# SectionD_v1_0.net
KiCad netlist of a schematic drawn in Altium Designer
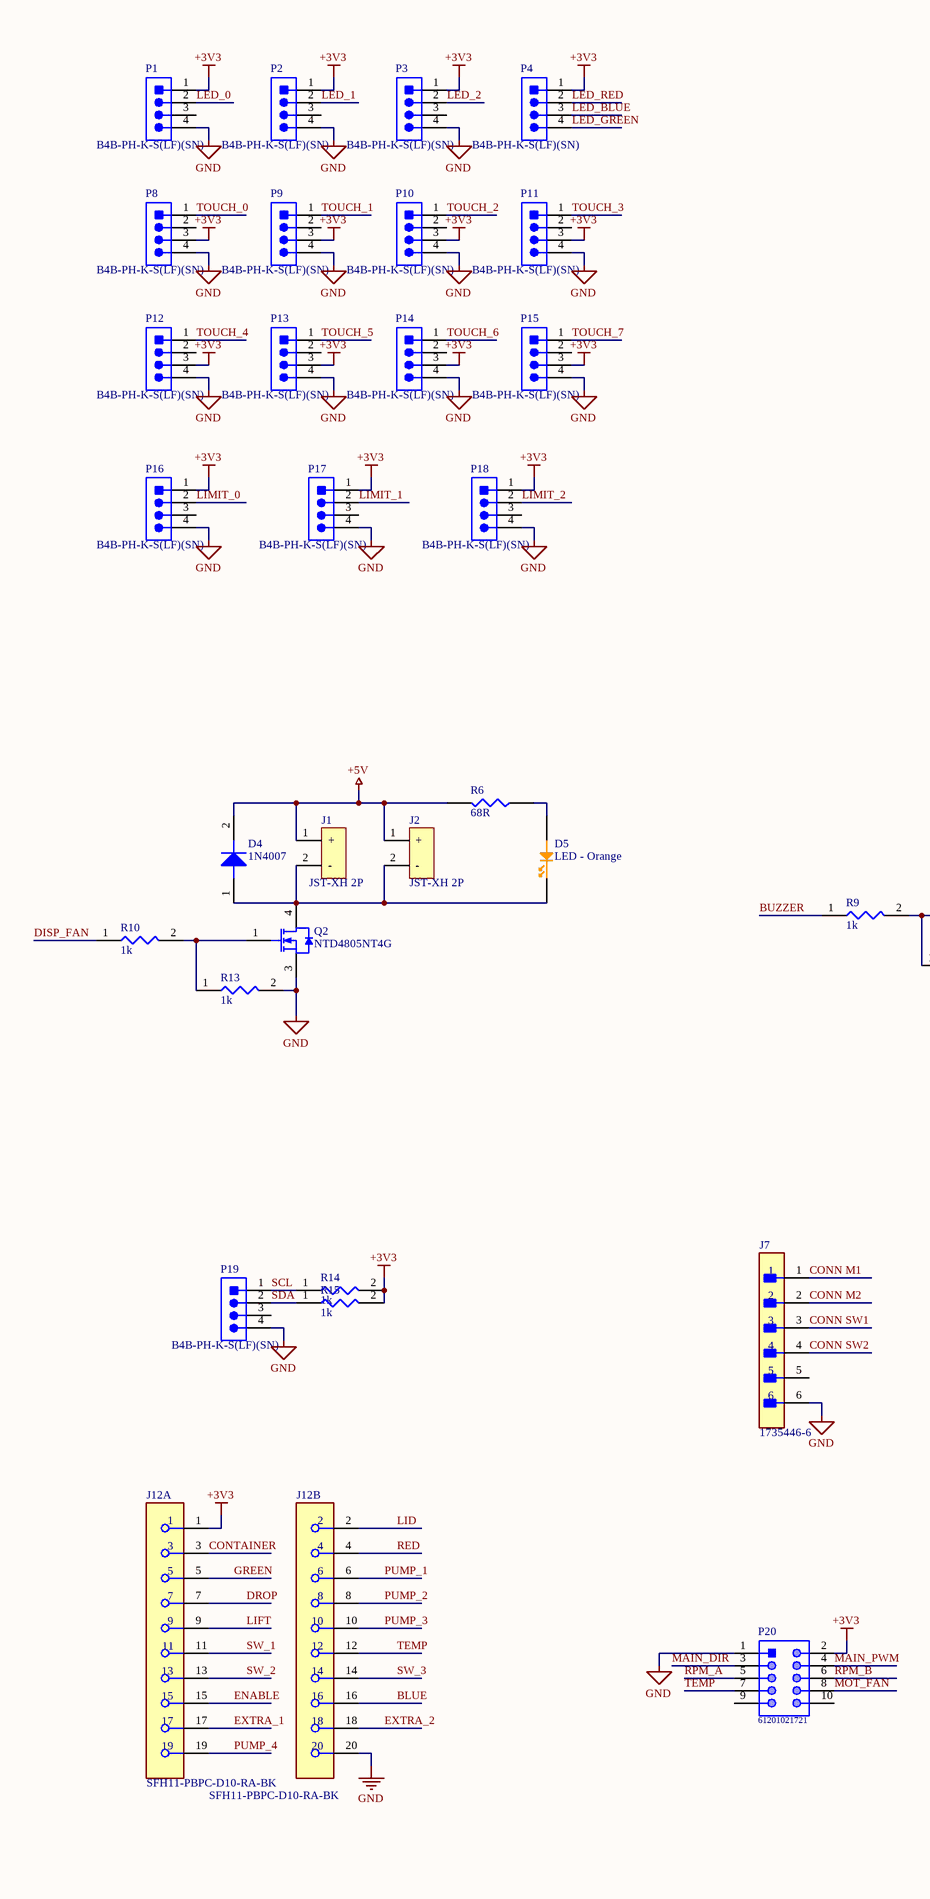
[diagram p0: SectionD_v1.0.SchDoc, left]
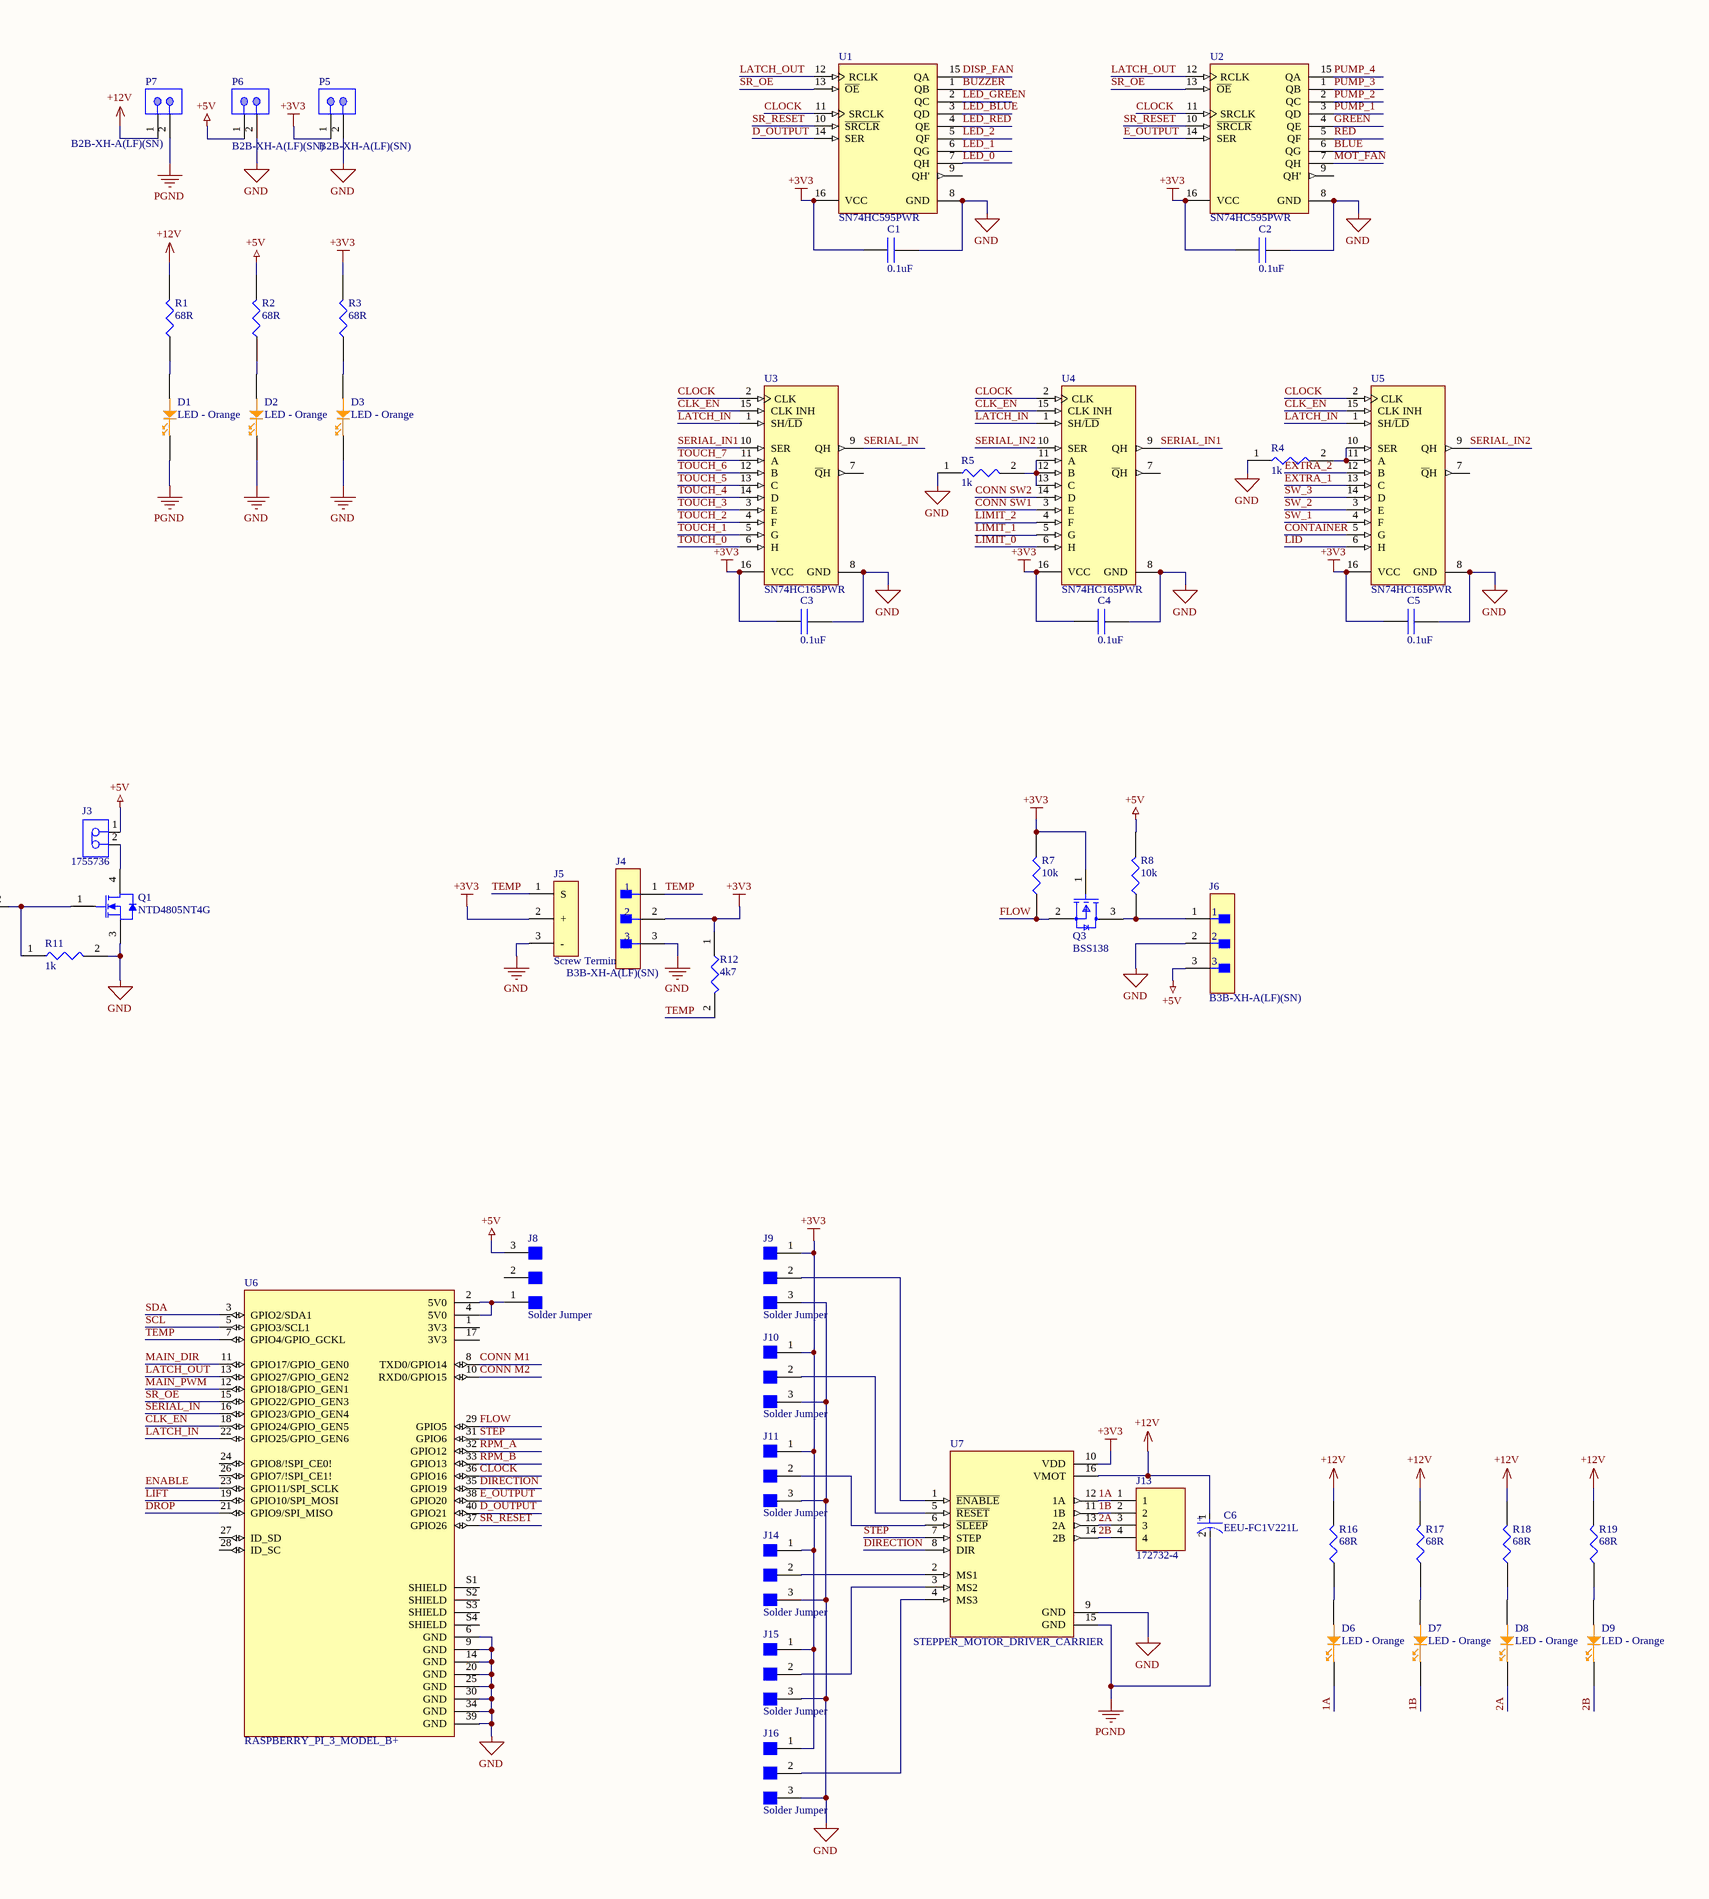
[diagram p1: SectionD_v1.0.SchDoc, right]

(export (version "E")
  (design (tool "Eeschema 10.0.6"))
  (components
    (comp (ref "C1")
      (value "0.1uF")
      (footprint "0.1uF 0603")
      (description "CAP CER 0.1UF 16V X7R 0603")
      (fields
        (field (name "MANUFACTURER") "KEMET")
        (field (name "MANUFACTURER PART NUMBER") "C0603C104M4RACTU")
      )
      (libsource (lib "Limit_Switch") (part "C0603C104M4RACTU"))
    )
    (comp (ref "C2")
      (value "0.1uF")
      (footprint "0.1uF 0603")
      (description "CAP CER 0.1UF 16V X7R 0603")
      (fields
        (field (name "MANUFACTURER") "KEMET")
        (field (name "MANUFACTURER PART NUMBER") "C0603C104M4RACTU")
      )
      (libsource (lib "Limit_Switch") (part "C0603C104M4RACTU"))
    )
    (comp (ref "C3")
      (value "0.1uF")
      (footprint "0.1uF 0603")
      (description "CAP CER 0.1UF 16V X7R 0603")
      (fields
        (field (name "MANUFACTURER") "KEMET")
        (field (name "MANUFACTURER PART NUMBER") "C0603C104M4RACTU")
      )
      (libsource (lib "Limit_Switch") (part "C0603C104M4RACTU"))
    )
    (comp (ref "C4")
      (value "0.1uF")
      (footprint "0.1uF 0603")
      (description "CAP CER 0.1UF 16V X7R 0603")
      (fields
        (field (name "MANUFACTURER") "KEMET")
        (field (name "MANUFACTURER PART NUMBER") "C0603C104M4RACTU")
      )
      (libsource (lib "Limit_Switch") (part "C0603C104M4RACTU"))
    )
    (comp (ref "C5")
      (value "0.1uF")
      (footprint "0.1uF 0603")
      (description "CAP CER 0.1UF 16V X7R 0603")
      (fields
        (field (name "MANUFACTURER") "KEMET")
        (field (name "MANUFACTURER PART NUMBER") "C0603C104M4RACTU")
      )
      (libsource (lib "Limit_Switch") (part "C0603C104M4RACTU"))
    )
    (comp (ref "C6")
      (value "EEU-FC1V221L")
      (footprint "FP-EEU-FC1V221L-MFG")
      (description "CAP ALUM 220UF 20% 35V RADIAL")
      (fields
        (field (name "OCTOPART") "https://octopart.com/eeu-fc1v221l-panasonic-39478519")
        (field (name "MANUFACTURER") "Panasonic Electronic Components")
      )
      (libsource (lib "Altium Content Vault") (part "385ce6c70a3ab0aa1e866f00bd8ed49"))
    )
    (comp (ref "D1")
      (value "LED - Orange")
      (footprint "LED0603-Orange")
      (description "LED ORANGE CLEAR SMD")
      (fields
        (field (name "MANUFACTURER") "Vishay Lite-On")
        (field (name "MANUFACTURER PART NUMBER") "LTST-C191KFKT")
      )
      (libsource (lib "SectionE_BreakOut") (part "LTST-C191KFKT"))
    )
    (comp (ref "D2")
      (value "LED - Orange")
      (footprint "LED0603-Orange")
      (description "LED ORANGE CLEAR SMD")
      (fields
        (field (name "MANUFACTURER") "Vishay Lite-On")
        (field (name "MANUFACTURER PART NUMBER") "LTST-C191KFKT")
      )
      (libsource (lib "SectionE_BreakOut") (part "LTST-C191KFKT"))
    )
    (comp (ref "D3")
      (value "LED - Orange")
      (footprint "LED0603-Orange")
      (description "LED ORANGE CLEAR SMD")
      (fields
        (field (name "MANUFACTURER") "Vishay Lite-On")
        (field (name "MANUFACTURER PART NUMBER") "LTST-C191KFKT")
      )
      (libsource (lib "SectionE_BreakOut") (part "LTST-C191KFKT"))
    )
    (comp (ref "D4")
      (value "1N4007")
      (footprint "M7 1N4007 SMA")
      (description "1000V 1A Rectifier")
      (fields
        (field (name "MANUFACTURER") "Sangdest Microelectronics")
        (field (name "MANUFACTURER PART NUMBER") "1N4007FLTR")
      )
      (libsource (lib "SectionE_BreakOut") (part "1N4007FLTR"))
    )
    (comp (ref "D5")
      (value "LED - Orange")
      (footprint "LED0603-Orange")
      (description "LED ORANGE CLEAR SMD")
      (fields
        (field (name "MANUFACTURER") "Vishay Lite-On")
        (field (name "MANUFACTURER PART NUMBER") "LTST-C191KFKT")
      )
      (libsource (lib "SectionE_BreakOut") (part "LTST-C191KFKT"))
    )
    (comp (ref "D6")
      (value "LED - Orange")
      (footprint "LED0603-Orange")
      (description "LED ORANGE CLEAR SMD")
      (fields
        (field (name "MANUFACTURER") "Vishay Lite-On")
        (field (name "MANUFACTURER PART NUMBER") "LTST-C191KFKT")
      )
      (libsource (lib "SectionE_BreakOut") (part "LTST-C191KFKT"))
    )
    (comp (ref "D7")
      (value "LED - Orange")
      (footprint "LED0603-Orange")
      (description "LED ORANGE CLEAR SMD")
      (fields
        (field (name "MANUFACTURER") "Vishay Lite-On")
        (field (name "MANUFACTURER PART NUMBER") "LTST-C191KFKT")
      )
      (libsource (lib "SectionE_BreakOut") (part "LTST-C191KFKT"))
    )
    (comp (ref "D8")
      (value "LED - Orange")
      (footprint "LED0603-Orange")
      (description "LED ORANGE CLEAR SMD")
      (fields
        (field (name "MANUFACTURER") "Vishay Lite-On")
        (field (name "MANUFACTURER PART NUMBER") "LTST-C191KFKT")
      )
      (libsource (lib "SectionE_BreakOut") (part "LTST-C191KFKT"))
    )
    (comp (ref "D9")
      (value "LED - Orange")
      (footprint "LED0603-Orange")
      (description "LED ORANGE CLEAR SMD")
      (fields
        (field (name "MANUFACTURER") "Vishay Lite-On")
        (field (name "MANUFACTURER PART NUMBER") "LTST-C191KFKT")
      )
      (libsource (lib "SectionE_BreakOut") (part "LTST-C191KFKT"))
    )
    (comp (ref "J1")
      (value "JST-XH 2P")
      (footprint "JST-XH 2P")
      (description "JST-XH 2 POS 2.5mm Solder ST Thru-Hole Box")
      (fields
        (field (name "MANUFACTURER") "JST")
        (field (name "MANUFACTURER PART NUMBER") "B2B-XH-A(LF)(SN)")
      )
      (libsource (lib "SectionE_BreakOut") (part "B2B-XH-A(LF)(SN)"))
    )
    (comp (ref "J2")
      (value "JST-XH 2P")
      (footprint "JST-XH 2P")
      (description "JST-XH 2 POS 2.5mm Solder ST Thru-Hole Box")
      (fields
        (field (name "MANUFACTURER") "JST")
        (field (name "MANUFACTURER PART NUMBER") "B2B-XH-A(LF)(SN)")
      )
      (libsource (lib "SectionE_BreakOut") (part "B2B-XH-A(LF)(SN)"))
    )
    (comp (ref "J3")
      (value "1755736")
      (footprint "PHOE-1755736-2_V")
      (description "Male Header, Pitch 5.08 mm, 1 x 2 Postion, Height 12 mm, Tail Length 3.9 mm, RoHS, Bulk")
      (fields (field (name "MANUFACTURER") "Phoenix Contact"))
      (libsource (lib "Altium Content Vault") (part "CN-2P-F-QF2"))
    )
    (comp (ref "J4")
      (value "B3B-XH-A(LF)(SN)")
      (footprint "FP-B3B-XH-A_LF_SN-MFG")
      (description "CONN HEADER VERT 3POS 2.5MM")
      (fields
        (field (name "OCTOPART") "https://octopart.com/b3b-xh-a%28lf%29%28sn%29-jst-3990185")
        (field (name "MANUFACTURER") "JST")
      )
      (libsource (lib "") (part "0d3f023dd272f625e17a2be33dea85f_1"))
    )
    (comp (ref "J5")
      (value "Screw Terminal")
      (footprint "Screw Terminal 3P 5.08MM")
      (description "TERM BLK 3P SIDE ENT 5.08MM PCB")
      (fields
        (field (name "MANUFACTURER") "On-Shore Technology")
        (field (name "MANUFACTURER PART NUMBER") "OSTTC032162")
      )
      (libsource (lib "SectionE_BreakOut") (part "OSTTC032162"))
    )
    (comp (ref "J6")
      (value "B3B-XH-A(LF)(SN)")
      (footprint "FP-B3B-XH-A_LF_SN-MFG")
      (description "CONN HEADER VERT 3POS 2.5MM")
      (fields
        (field (name "OCTOPART") "https://octopart.com/b3b-xh-a%28lf%29%28sn%29-jst-3990185")
        (field (name "MANUFACTURER") "JST")
      )
      (libsource (lib "Altium Content Vault") (part "0d3f023dd272f625e17a2be33dea85f"))
    )
    (comp (ref "J7")
      (value "1735446-6")
      (footprint "FP-1735446-6-MFG")
      (description "CONN HEADER VERT 6POS 2MM")
      (fields
        (field (name "MANUFACTURER") "TE")
        (field (name "OCTOPART") "https://octopart.com/1735446-6-te+connectivity-42205942")
      )
      (libsource (lib "Altium Content Vault") (part "f2cb566baf1c37ab5a3b8e90bbeafd6"))
    )
    (comp (ref "J8")
      (value "Solder Jumper")
      (footprint "Solder Jumper")
      (libsource (lib "SectionE_BreakOut") (part "Solder Jumper"))
    )
    (comp (ref "J9")
      (value "Solder Jumper")
      (footprint "Solder Jumper")
      (libsource (lib "SectionE_BreakOut") (part "Solder Jumper"))
    )
    (comp (ref "J10")
      (value "Solder Jumper")
      (footprint "Solder Jumper")
      (libsource (lib "SectionE_BreakOut") (part "Solder Jumper"))
    )
    (comp (ref "J11")
      (value "Solder Jumper")
      (footprint "Solder Jumper")
      (libsource (lib "SectionE_BreakOut") (part "Solder Jumper"))
    )
    (comp (ref "J12")
      (value "SFH11-PBPC-D10-RA-BK")
      (footprint "FP-SFH11-PBPC-D10-RA-BK-MFG")
      (description "CONN HDR 20POS 0.1 GOLD PCB R/A")
      (fields
        (field (name "OCTOPART") "https://octopart.com/sfh11-pbpc-d10-ra-bk-sullins-12270496")
        (field (name "MANUFACTURER") "Sullins")
      )
      (libsource (lib "Altium Content Vault") (part "86e307fb827e6da12e54f1dde2f44ab"))
    )
    (comp (ref "J13")
      (value "172732-4")
      (footprint "TE_172732-4")
      (description "EIS POST HDR WITH KINK 10P")
      (libsource (lib "172732-4") (part "172732-4"))
    )
    (comp (ref "J14")
      (value "Solder Jumper")
      (footprint "Solder Jumper")
      (libsource (lib "SectionE_BreakOut") (part "Solder Jumper"))
    )
    (comp (ref "J15")
      (value "Solder Jumper")
      (footprint "Solder Jumper")
      (libsource (lib "SectionE_BreakOut") (part "Solder Jumper"))
    )
    (comp (ref "J16")
      (value "Solder Jumper")
      (footprint "Solder Jumper")
      (libsource (lib "SectionE_BreakOut") (part "Solder Jumper"))
    )
    (comp (ref "P1")
      (value "B4B-PH-K-S(LF)(SN)")
      (footprint "JST-B4B-PH-K-S_V")
      (fields (field (name "MANUFACTURER") "JST"))
      (libsource (lib "Altium Content Vault") (part "CN-1P-M-R4"))
    )
    (comp (ref "P2")
      (value "B4B-PH-K-S(LF)(SN)")
      (footprint "JST-B4B-PH-K-S_V")
      (fields (field (name "MANUFACTURER") "JST"))
      (libsource (lib "Altium Content Vault") (part "CN-1P-M-R4"))
    )
    (comp (ref "P3")
      (value "B4B-PH-K-S(LF)(SN)")
      (footprint "JST-B4B-PH-K-S_V")
      (fields (field (name "MANUFACTURER") "JST"))
      (libsource (lib "Altium Content Vault") (part "CN-1P-M-R4"))
    )
    (comp (ref "P4")
      (value "B4B-PH-K-S(LF)(SN)")
      (footprint "JST-B4B-PH-K-S_V")
      (fields (field (name "MANUFACTURER") "JST"))
      (libsource (lib "Altium Content Vault") (part "CN-1P-M-R4"))
    )
    (comp (ref "P5")
      (value "B2B-XH-A(LF)(SN)")
      (footprint "JST-B2B-XH-A_V")
      (fields (field (name "MANUFACTURER") "JST"))
      (libsource (lib "Altium Content Vault") (part "CN-1P-M-R2"))
    )
    (comp (ref "P6")
      (value "B2B-XH-A(LF)(SN)")
      (footprint "JST-B2B-XH-A_V")
      (fields (field (name "MANUFACTURER") "JST"))
      (libsource (lib "Altium Content Vault") (part "CN-1P-M-R2"))
    )
    (comp (ref "P7")
      (value "B2B-XH-A(LF)(SN)")
      (footprint "JST-B2B-XH-A_V")
      (fields (field (name "MANUFACTURER") "JST"))
      (libsource (lib "Altium Content Vault") (part "CN-1P-M-R2"))
    )
    (comp (ref "P8")
      (value "B4B-PH-K-S(LF)(SN)")
      (footprint "JST-B4B-PH-K-S_V")
      (fields (field (name "MANUFACTURER") "JST"))
      (libsource (lib "Altium Content Vault") (part "CN-1P-M-R4"))
    )
    (comp (ref "P9")
      (value "B4B-PH-K-S(LF)(SN)")
      (footprint "JST-B4B-PH-K-S_V")
      (fields (field (name "MANUFACTURER") "JST"))
      (libsource (lib "Altium Content Vault") (part "CN-1P-M-R4"))
    )
    (comp (ref "P10")
      (value "B4B-PH-K-S(LF)(SN)")
      (footprint "JST-B4B-PH-K-S_V")
      (fields (field (name "MANUFACTURER") "JST"))
      (libsource (lib "Altium Content Vault") (part "CN-1P-M-R4"))
    )
    (comp (ref "P11")
      (value "B4B-PH-K-S(LF)(SN)")
      (footprint "JST-B4B-PH-K-S_V")
      (fields (field (name "MANUFACTURER") "JST"))
      (libsource (lib "Altium Content Vault") (part "CN-1P-M-R4"))
    )
    (comp (ref "P12")
      (value "B4B-PH-K-S(LF)(SN)")
      (footprint "JST-B4B-PH-K-S_V")
      (fields (field (name "MANUFACTURER") "JST"))
      (libsource (lib "Altium Content Vault") (part "CN-1P-M-R4"))
    )
    (comp (ref "P13")
      (value "B4B-PH-K-S(LF)(SN)")
      (footprint "JST-B4B-PH-K-S_V")
      (fields (field (name "MANUFACTURER") "JST"))
      (libsource (lib "Altium Content Vault") (part "CN-1P-M-R4"))
    )
    (comp (ref "P14")
      (value "B4B-PH-K-S(LF)(SN)")
      (footprint "JST-B4B-PH-K-S_V")
      (fields (field (name "MANUFACTURER") "JST"))
      (libsource (lib "Altium Content Vault") (part "CN-1P-M-R4"))
    )
    (comp (ref "P15")
      (value "B4B-PH-K-S(LF)(SN)")
      (footprint "JST-B4B-PH-K-S_V")
      (fields (field (name "MANUFACTURER") "JST"))
      (libsource (lib "Altium Content Vault") (part "CN-1P-M-R4"))
    )
    (comp (ref "P16")
      (value "B4B-PH-K-S(LF)(SN)")
      (footprint "JST-B4B-PH-K-S_V")
      (fields (field (name "MANUFACTURER") "JST"))
      (libsource (lib "Altium Content Vault") (part "CN-1P-M-R4"))
    )
    (comp (ref "P17")
      (value "B4B-PH-K-S(LF)(SN)")
      (footprint "JST-B4B-PH-K-S_V")
      (fields (field (name "MANUFACTURER") "JST"))
      (libsource (lib "Altium Content Vault") (part "CN-1P-M-R4"))
    )
    (comp (ref "P18")
      (value "B4B-PH-K-S(LF)(SN)")
      (footprint "JST-B4B-PH-K-S_V")
      (fields (field (name "MANUFACTURER") "JST"))
      (libsource (lib "Altium Content Vault") (part "CN-1P-M-R4"))
    )
    (comp (ref "P19")
      (value "B4B-PH-K-S(LF)(SN)")
      (footprint "JST-B4B-PH-K-S_V")
      (fields (field (name "MANUFACTURER") "JST"))
      (libsource (lib "Altium Content Vault") (part "CN-1P-M-R4"))
    )
    (comp (ref "P20")
      (value "61201021721")
      (footprint "61201021721")
      (description "Male Box Header WR-BHD, THT, Angled, pitch 2.54 mm, 10 pins")
      (fields (field (name "MANUFACTURER") "Wurth Elektronik") (field (name "PUBLISHER") "WurthElektronik"))
      (libsource (lib "Altium Content Vault") (part "WE-CN-2P-M-R10"))
    )
    (comp (ref "Q1")
      (value "NTD4805NT4G")
      (footprint "ONSC-DPAK-3-369AA-01_V")
      (description "Power MOSFET, 30 V, 88 A, Single N-Channel, 3-Pin DPAK, Pb-Free, Tape and Reel")
      (fields (field (name "MANUFACTURER") "On Semiconductor"))
      (libsource (lib "Altium Content Vault") (part "ONSC-NMOS-G1S3D4-3_B"))
    )
    (comp (ref "Q2")
      (value "NTD4805NT4G")
      (footprint "ONSC-DPAK-3-369AA-01_V")
      (description "Power MOSFET, 30 V, 88 A, Single N-Channel, 3-Pin DPAK, Pb-Free, Tape and Reel")
      (fields (field (name "MANUFACTURER") "On Semiconductor"))
      (libsource (lib "Altium Content Vault") (part "ONSC-NMOS-G1S3D4-3_B"))
    )
    (comp (ref "Q3")
      (value "BSS138")
      (footprint "FP-318-08-IPC_B")
      (description "MOSFET N-CH 50V 220MA SOT-23")
      (libsource (lib "Altium Content Vault") (part "3b9c635fedb024a5347a57b145af9cc"))
    )
    (comp (ref "R1")
      (value "68R")
      (footprint "68R 0603")
      (description "CRGP 0603 68R 1%")
      (fields
        (field (name "MANUFACTURER") "TE Connectivity")
        (field (name "MANUFACTURER PART NUMBER") "CRGP0603F68R")
      )
      (libsource (lib "SectionE_BreakOut") (part "CRGP0603F68R"))
    )
    (comp (ref "R2")
      (value "68R")
      (footprint "68R 0603")
      (description "CRGP 0603 68R 1%")
      (fields
        (field (name "MANUFACTURER") "TE Connectivity")
        (field (name "MANUFACTURER PART NUMBER") "CRGP0603F68R")
      )
      (libsource (lib "SectionE_BreakOut") (part "CRGP0603F68R"))
    )
    (comp (ref "R3")
      (value "68R")
      (footprint "68R 0603")
      (description "CRGP 0603 68R 1%")
      (fields
        (field (name "MANUFACTURER") "TE Connectivity")
        (field (name "MANUFACTURER PART NUMBER") "CRGP0603F68R")
      )
      (libsource (lib "SectionE_BreakOut") (part "CRGP0603F68R"))
    )
    (comp (ref "R4")
      (value "1k")
      (footprint "R0603 1k")
      (description "0603 1k Ohm 1% 1/10W")
      (fields
        (field (name "MANUFACTURER") "TE Connectivity")
        (field (name "MANUFACTURER PART NUMBER") "CRGCQ0603F1K0")
      )
      (libsource (lib "SectionE_BreakOut") (part "CRGCQ0603F1K0"))
    )
    (comp (ref "R5")
      (value "1k")
      (footprint "R0603 1k")
      (description "0603 1k Ohm 1% 1/10W")
      (fields
        (field (name "MANUFACTURER") "TE Connectivity")
        (field (name "MANUFACTURER PART NUMBER") "CRGCQ0603F1K0")
      )
      (libsource (lib "SectionE_BreakOut") (part "CRGCQ0603F1K0"))
    )
    (comp (ref "R6")
      (value "68R")
      (footprint "68R 0603")
      (description "CRGP 0603 68R 1%")
      (fields
        (field (name "MANUFACTURER") "TE Connectivity")
        (field (name "MANUFACTURER PART NUMBER") "CRGP0603F68R")
      )
      (libsource (lib "SectionE_BreakOut") (part "CRGP0603F68R"))
    )
    (comp (ref "R7")
      (value "10k")
      (footprint "10k R0603")
      (description "RES 10.0K OHM 1/10W 1% 0603")
      (fields
        (field (name "MANUFACTURER") "TE Connectivity")
        (field (name "MANUFACTURER PART NUMBER") "CRG0603F10K/10")
      )
      (libsource (lib "Limit_Switch_RGB") (part "CRG0603F10K/10"))
    )
    (comp (ref "R8")
      (value "10k")
      (footprint "10k R0603")
      (description "RES 10.0K OHM 1/10W 1% 0603")
      (fields
        (field (name "MANUFACTURER") "TE Connectivity")
        (field (name "MANUFACTURER PART NUMBER") "CRG0603F10K/10")
      )
      (libsource (lib "Limit_Switch_RGB") (part "CRG0603F10K/10"))
    )
    (comp (ref "R9")
      (value "1k")
      (footprint "R0603 1k")
      (description "0603 1k Ohm 1% 1/10W")
      (fields
        (field (name "MANUFACTURER") "TE Connectivity")
        (field (name "MANUFACTURER PART NUMBER") "CRGCQ0603F1K0")
      )
      (libsource (lib "SectionE_BreakOut") (part "CRGCQ0603F1K0"))
    )
    (comp (ref "R10")
      (value "1k")
      (footprint "R0603 1k")
      (description "0603 1k Ohm 1% 1/10W")
      (fields
        (field (name "MANUFACTURER") "TE Connectivity")
        (field (name "MANUFACTURER PART NUMBER") "CRGCQ0603F1K0")
      )
      (libsource (lib "SectionE_BreakOut") (part "CRGCQ0603F1K0"))
    )
    (comp (ref "R11")
      (value "1k")
      (footprint "R0603 1k")
      (description "0603 1k Ohm 1% 1/10W")
      (fields
        (field (name "MANUFACTURER") "TE Connectivity")
        (field (name "MANUFACTURER PART NUMBER") "CRGCQ0603F1K0")
      )
      (libsource (lib "SectionE_BreakOut") (part "CRGCQ0603F1K0"))
    )
    (comp (ref "R12")
      (value "4k7")
      (footprint "R0603 1k")
      (description "0603 1k Ohm 1% 1/10W")
      (fields
        (field (name "MANUFACTURER") "TE Connectivity")
        (field (name "MANUFACTURER PART NUMBER") "CRGCQ0603F1K0")
      )
      (libsource (lib "SectionE_BreakOut") (part "CRGCQ0603F1K0"))
    )
    (comp (ref "R13")
      (value "1k")
      (footprint "R0603 1k")
      (description "0603 1k Ohm 1% 1/10W")
      (fields
        (field (name "MANUFACTURER") "TE Connectivity")
        (field (name "MANUFACTURER PART NUMBER") "CRGCQ0603F1K0")
      )
      (libsource (lib "SectionE_BreakOut") (part "CRGCQ0603F1K0"))
    )
    (comp (ref "R14")
      (value "1k")
      (footprint "R0603 1k")
      (description "0603 1k Ohm 1% 1/10W")
      (fields
        (field (name "MANUFACTURER") "TE Connectivity")
        (field (name "MANUFACTURER PART NUMBER") "CRGCQ0603F1K0")
      )
      (libsource (lib "SectionE_BreakOut") (part "CRGCQ0603F1K0"))
    )
    (comp (ref "R15")
      (value "1k")
      (footprint "R0603 1k")
      (description "0603 1k Ohm 1% 1/10W")
      (fields
        (field (name "MANUFACTURER") "TE Connectivity")
        (field (name "MANUFACTURER PART NUMBER") "CRGCQ0603F1K0")
      )
      (libsource (lib "SectionE_BreakOut") (part "CRGCQ0603F1K0"))
    )
    (comp (ref "R16")
      (value "68R")
      (footprint "68R 0603")
      (description "CRGP 0603 68R 1%")
      (fields
        (field (name "MANUFACTURER") "TE Connectivity")
        (field (name "MANUFACTURER PART NUMBER") "CRGP0603F68R")
      )
      (libsource (lib "SectionE_BreakOut") (part "CRGP0603F68R"))
    )
    (comp (ref "R17")
      (value "68R")
      (footprint "68R 0603")
      (description "CRGP 0603 68R 1%")
      (fields
        (field (name "MANUFACTURER") "TE Connectivity")
        (field (name "MANUFACTURER PART NUMBER") "CRGP0603F68R")
      )
      (libsource (lib "SectionE_BreakOut") (part "CRGP0603F68R"))
    )
    (comp (ref "R18")
      (value "68R")
      (footprint "68R 0603")
      (description "CRGP 0603 68R 1%")
      (fields
        (field (name "MANUFACTURER") "TE Connectivity")
        (field (name "MANUFACTURER PART NUMBER") "CRGP0603F68R")
      )
      (libsource (lib "SectionE_BreakOut") (part "CRGP0603F68R"))
    )
    (comp (ref "R19")
      (value "68R")
      (footprint "68R 0603")
      (description "CRGP 0603 68R 1%")
      (fields
        (field (name "MANUFACTURER") "TE Connectivity")
        (field (name "MANUFACTURER PART NUMBER") "CRGP0603F68R")
      )
      (libsource (lib "SectionE_BreakOut") (part "CRGP0603F68R"))
    )
    (comp (ref "U1")
      (value "SN74HC595PWR")
      (footprint "PW0016A_N")
      (description "8-Bit Shift Registers With 3-State Output Registers, PW0016A, LARGE T&R")
      (fields
        (field (name "GENERIC PART NUMBER") "SN74HC595")
        (field (name "MANUFACTURER") "Texas Instruments")
      )
      (libsource (lib "Altium Content Vault") (part "TI-SN74XHCT595X_SN74LV595A-16"))
    )
    (comp (ref "U2")
      (value "SN74HC595PWR")
      (footprint "PW0016A_N")
      (description "8-Bit Shift Registers With 3-State Output Registers, PW0016A, LARGE T&R")
      (fields
        (field (name "GENERIC PART NUMBER") "SN74HC595")
        (field (name "MANUFACTURER") "Texas Instruments")
      )
      (libsource (lib "Altium Content Vault") (part "TI-SN74XHCT595X_SN74LV595A-16"))
    )
    (comp (ref "U3")
      (value "SN74HC165PWR")
      (footprint "PW0016A_N")
      (description "8-Bit Parallel-Load Shift Registers, PW0016A, LARGE T&R")
      (fields
        (field (name "GENERIC PART NUMBER") "SN74HC165")
        (field (name "MANUFACTURER") "Texas Instruments")
      )
      (libsource (lib "Altium Content Vault") (part "TI-SNX4XXX165X-16"))
    )
    (comp (ref "U4")
      (value "SN74HC165PWR")
      (footprint "PW0016A_N")
      (description "8-Bit Parallel-Load Shift Registers, PW0016A, LARGE T&R")
      (fields
        (field (name "GENERIC PART NUMBER") "SN74HC165")
        (field (name "MANUFACTURER") "Texas Instruments")
      )
      (libsource (lib "Altium Content Vault") (part "TI-SNX4XXX165X-16"))
    )
    (comp (ref "U5")
      (value "SN74HC165PWR")
      (footprint "PW0016A_N")
      (description "8-Bit Parallel-Load Shift Registers, PW0016A, LARGE T&R")
      (fields
        (field (name "GENERIC PART NUMBER") "SN74HC165")
        (field (name "MANUFACTURER") "Texas Instruments")
      )
      (libsource (lib "Altium Content Vault") (part "TI-SNX4XXX165X-16"))
    )
    (comp (ref "U6")
      (value "RASPBERRY_PI_3_MODEL_B+")
      (footprint "MODULE_RASPBERRY_PI_3_MODEL_B+:MODULE_RASPBERRY_PI_3_MODEL_B+")
      (description "BCM2837B0 Raspberry Pi 3 Model B+ - ARMÂ® CortexÂ®-A53, VideoCore MPU Embedded Evaluation Board")
      (fields (field (name "MP") "RASPBERRY PI 3 MODEL B+") (field (name "MF") "Raspberry Pi"))
      (libsource (lib "RASPBERRY_PI_3_MODEL_B+") (part "RASPBERRY_PI_3_MODEL_B+"))
    )
    (comp (ref "U7")
      (value "STEPPER_MOTOR_DRIVER_CARRIER")
      (footprint "MODULE_A4988_STEPPER_MOTOR_DRIVER_CARRIER")
      (description "Stepper Motor Driver")
      (fields (field (name "MP") "A4988 STEPPER MOTOR DRIVER CARRIER") (field (name "MF") "Pololu"))
      (libsource (lib "A4988_STEPPER_MOTOR_DRIVER_CARRIER") (part "A4988_STEPPER_MOTOR_DRIVER_CARRIER"))
    )
  )
  (nets
    (net (code "1") (name "+3V3") (class "Default")
      (node (ref "C1") (pin "2") (pinfunction "2_2") (pintype "passive"))
      (node (ref "C2") (pin "2") (pinfunction "2_2") (pintype "passive"))
      (node (ref "C3") (pin "2") (pinfunction "2_2") (pintype "passive"))
      (node (ref "C4") (pin "2") (pinfunction "2_2") (pintype "passive"))
      (node (ref "C5") (pin "2") (pinfunction "2_2") (pintype "passive"))
      (node (ref "J10") (pin "1") (pinfunction "1_1") (pintype "passive"))
      (node (ref "J11") (pin "1") (pinfunction "1_1") (pintype "passive"))
      (node (ref "J12") (pin "1") (pinfunction "1_1") (pintype "passive"))
      (node (ref "J14") (pin "1") (pinfunction "1_1") (pintype "passive"))
      (node (ref "J15") (pin "1") (pinfunction "1_1") (pintype "passive"))
      (node (ref "J16") (pin "1") (pinfunction "1_1") (pintype "passive"))
      (node (ref "J4") (pin "2") (pinfunction "2_2") (pintype "passive"))
      (node (ref "J5") (pin "2") (pinfunction "+_2") (pintype "passive"))
      (node (ref "J9") (pin "1") (pinfunction "1_1") (pintype "passive"))
      (node (ref "P1") (pin "1") (pinfunction "1_1") (pintype "passive"))
      (node (ref "P10") (pin "3") (pinfunction "3_3") (pintype "passive"))
      (node (ref "P11") (pin "3") (pinfunction "3_3") (pintype "passive"))
      (node (ref "P12") (pin "3") (pinfunction "3_3") (pintype "passive"))
      (node (ref "P13") (pin "3") (pinfunction "3_3") (pintype "passive"))
      (node (ref "P14") (pin "3") (pinfunction "3_3") (pintype "passive"))
      (node (ref "P15") (pin "3") (pinfunction "3_3") (pintype "passive"))
      (node (ref "P16") (pin "1") (pinfunction "1_1") (pintype "passive"))
      (node (ref "P17") (pin "1") (pinfunction "1_1") (pintype "passive"))
      (node (ref "P18") (pin "1") (pinfunction "1_1") (pintype "passive"))
      (node (ref "P2") (pin "1") (pinfunction "1_1") (pintype "passive"))
      (node (ref "P20") (pin "2") (pinfunction "2_2") (pintype "passive"))
      (node (ref "P3") (pin "1") (pinfunction "1_1") (pintype "passive"))
      (node (ref "P4") (pin "1") (pinfunction "1_1") (pintype "passive"))
      (node (ref "P5") (pin "1") (pinfunction "1_1") (pintype "passive"))
      (node (ref "P8") (pin "3") (pinfunction "3_3") (pintype "passive"))
      (node (ref "P9") (pin "3") (pinfunction "3_3") (pintype "passive"))
      (node (ref "Q3") (pin "1") (pinfunction "G_1") (pintype "passive"))
      (node (ref "R12") (pin "1") (pinfunction "1_1") (pintype "passive"))
      (node (ref "R14") (pin "2") (pinfunction "2_2") (pintype "passive"))
      (node (ref "R15") (pin "2") (pinfunction "2_2") (pintype "passive"))
      (node (ref "R3") (pin "2") (pinfunction "2_2") (pintype "passive"))
      (node (ref "R7") (pin "2") (pinfunction "2_2") (pintype "passive"))
      (node (ref "U1") (pin "16") (pinfunction "VCC_16") (pintype "power_in"))
      (node (ref "U2") (pin "16") (pinfunction "VCC_16") (pintype "power_in"))
      (node (ref "U3") (pin "16") (pinfunction "VCC_16") (pintype "power_in"))
      (node (ref "U4") (pin "16") (pinfunction "VCC_16") (pintype "power_in"))
      (node (ref "U5") (pin "16") (pinfunction "VCC_16") (pintype "power_in"))
      (node (ref "U7") (pin "10") (pinfunction "VDD_10") (pintype "power_in"))
    )
    (net (code "2") (name "+5V") (class "Default")
      (node (ref "D4") (pin "2") (pinfunction "Cathode_2") (pintype "passive"))
      (node (ref "J1") (pin "1") (pinfunction "+_1") (pintype "passive"))
      (node (ref "J2") (pin "1") (pinfunction "+_1") (pintype "passive"))
      (node (ref "J3") (pin "1") (pinfunction "1_1") (pintype "passive"))
      (node (ref "J6") (pin "3") (pinfunction "3_3") (pintype "passive"))
      (node (ref "J8") (pin "3") (pinfunction "3_3") (pintype "passive"))
      (node (ref "P6") (pin "1") (pinfunction "1_1") (pintype "passive"))
      (node (ref "R2") (pin "2") (pinfunction "2_2") (pintype "passive"))
      (node (ref "R6") (pin "2") (pinfunction "2_2") (pintype "passive"))
      (node (ref "R8") (pin "2") (pinfunction "2_2") (pintype "passive"))
    )
    (net (code "3") (name "+12V") (class "Default")
      (node (ref "C6") (pin "1") (pinfunction "C_1") (pintype "passive"))
      (node (ref "P7") (pin "1") (pinfunction "1_1") (pintype "passive"))
      (node (ref "R1") (pin "2") (pinfunction "2_2") (pintype "passive"))
      (node (ref "R16") (pin "2") (pinfunction "2_2") (pintype "passive"))
      (node (ref "R17") (pin "2") (pinfunction "2_2") (pintype "passive"))
      (node (ref "R18") (pin "2") (pinfunction "2_2") (pintype "passive"))
      (node (ref "R19") (pin "2") (pinfunction "2_2") (pintype "passive"))
      (node (ref "U7") (pin "16") (pinfunction "VMOT_16") (pintype "power_in"))
    )
    (net (code "4") (name "/1A") (class "Default")
      (node (ref "D6") (pin "1") (pinfunction "Cathode_1") (pintype "passive"))
      (node (ref "J13") (pin "1") (pinfunction "1_1") (pintype "passive"))
      (node (ref "U7") (pin "12") (pinfunction "1A_12") (pintype "output"))
    )
    (net (code "5") (name "/1B") (class "Default")
      (node (ref "D7") (pin "1") (pinfunction "Cathode_1") (pintype "passive"))
      (node (ref "J13") (pin "2") (pinfunction "2_2") (pintype "passive"))
      (node (ref "U7") (pin "11") (pinfunction "1B_11") (pintype "output"))
    )
    (net (code "6") (name "/2A") (class "Default")
      (node (ref "D8") (pin "1") (pinfunction "Cathode_1") (pintype "passive"))
      (node (ref "J13") (pin "3") (pinfunction "3_3") (pintype "passive"))
      (node (ref "U7") (pin "13") (pinfunction "2A_13") (pintype "output"))
    )
    (net (code "7") (name "/2B") (class "Default")
      (node (ref "D9") (pin "1") (pinfunction "Cathode_1") (pintype "passive"))
      (node (ref "J13") (pin "4") (pinfunction "4_4") (pintype "passive"))
      (node (ref "U7") (pin "14") (pinfunction "2B_14") (pintype "output"))
    )
    (net (code "8") (name "/BLUE") (class "Default")
      (node (ref "J12") (pin "16") (pinfunction "16_16") (pintype "passive"))
      (node (ref "U2") (pin "6") (pinfunction "QG_6") (pintype "tri_state"))
    )
    (net (code "9") (name "/BUZZER") (class "Default")
      (node (ref "R9") (pin "1") (pinfunction "1_1") (pintype "passive"))
      (node (ref "U1") (pin "1") (pinfunction "QB_1") (pintype "tri_state"))
    )
    (net (code "10") (name "/CLK_EN") (class "Default")
      (node (ref "U3") (pin "15") (pinfunction "CLK_INH_15") (pintype "input"))
      (node (ref "U4") (pin "15") (pinfunction "CLK_INH_15") (pintype "input"))
      (node (ref "U5") (pin "15") (pinfunction "CLK_INH_15") (pintype "input"))
      (node (ref "U6") (pin "18") (pinfunction "GPIO24/GPIO_GEN5_18") (pintype "bidirectional"))
    )
    (net (code "11") (name "/CLOCK") (class "Default")
      (node (ref "U1") (pin "11") (pinfunction "SRCLK_11") (pintype "input"))
      (node (ref "U2") (pin "11") (pinfunction "SRCLK_11") (pintype "input"))
      (node (ref "U3") (pin "2") (pinfunction "CLK_2") (pintype "input"))
      (node (ref "U4") (pin "2") (pinfunction "CLK_2") (pintype "input"))
      (node (ref "U5") (pin "2") (pinfunction "CLK_2") (pintype "input"))
      (node (ref "U6") (pin "36") (pinfunction "GPIO16_36") (pintype "bidirectional"))
    )
    (net (code "12") (name "/CONN M1") (class "Default")
      (node (ref "J7") (pin "1") (pinfunction "1_1") (pintype "passive"))
      (node (ref "U6") (pin "8") (pinfunction "TXD0/GPIO14_8") (pintype "bidirectional"))
    )
    (net (code "13") (name "/CONN M2") (class "Default")
      (node (ref "J7") (pin "2") (pinfunction "2_2") (pintype "passive"))
      (node (ref "U6") (pin "10") (pinfunction "RXD0/GPIO15_10") (pintype "bidirectional"))
    )
    (net (code "14") (name "/CONN SW1") (class "Default")
      (node (ref "J7") (pin "3") (pinfunction "3_3") (pintype "passive"))
      (node (ref "U4") (pin "3") (pinfunction "E_3") (pintype "input"))
    )
    (net (code "15") (name "/CONN SW2") (class "Default")
      (node (ref "J7") (pin "4") (pinfunction "4_4") (pintype "passive"))
      (node (ref "U4") (pin "14") (pinfunction "D_14") (pintype "input"))
    )
    (net (code "16") (name "/CONTAINER") (class "Default")
      (node (ref "J12") (pin "3") (pinfunction "3_3") (pintype "passive"))
      (node (ref "U5") (pin "5") (pinfunction "G_5") (pintype "input"))
    )
    (net (code "17") (name "/DIRECTION") (class "Default")
      (node (ref "U6") (pin "35") (pinfunction "GPIO19_35") (pintype "bidirectional"))
      (node (ref "U7") (pin "8") (pinfunction "DIR_8") (pintype "input"))
    )
    (net (code "18") (name "/DISP_FAN") (class "Default")
      (node (ref "R10") (pin "1") (pinfunction "1_1") (pintype "passive"))
      (node (ref "U1") (pin "15") (pinfunction "QA_15") (pintype "tri_state"))
    )
    (net (code "19") (name "/DROP") (class "Default")
      (node (ref "J12") (pin "7") (pinfunction "7_7") (pintype "passive"))
      (node (ref "U6") (pin "21") (pinfunction "GPIO9/SPI_MISO_21") (pintype "bidirectional"))
    )
    (net (code "20") (name "/D_OUTPUT") (class "Default")
      (node (ref "U1") (pin "14") (pinfunction "SER_14") (pintype "input"))
      (node (ref "U6") (pin "40") (pinfunction "GPIO21_40") (pintype "bidirectional"))
    )
    (net (code "21") (name "/ENABLE") (class "Default")
      (node (ref "J12") (pin "15") (pinfunction "15_15") (pintype "passive"))
      (node (ref "U6") (pin "23") (pinfunction "GPIO11/SPI_SCLK_23") (pintype "bidirectional"))
    )
    (net (code "22") (name "/EXTRA_1") (class "Default")
      (node (ref "J12") (pin "17") (pinfunction "17_17") (pintype "passive"))
      (node (ref "U5") (pin "13") (pinfunction "C_13") (pintype "input"))
    )
    (net (code "23") (name "/EXTRA_2") (class "Default")
      (node (ref "J12") (pin "18") (pinfunction "18_18") (pintype "passive"))
      (node (ref "U5") (pin "12") (pinfunction "B_12") (pintype "input"))
    )
    (net (code "24") (name "/E_OUTPUT") (class "Default")
      (node (ref "U2") (pin "14") (pinfunction "SER_14") (pintype "input"))
      (node (ref "U6") (pin "38") (pinfunction "GPIO20_38") (pintype "bidirectional"))
    )
    (net (code "25") (name "/FLOW") (class "Default")
      (node (ref "Q3") (pin "2") (pinfunction "S_2") (pintype "passive"))
      (node (ref "R7") (pin "1") (pinfunction "1_1") (pintype "passive"))
      (node (ref "U6") (pin "29") (pinfunction "GPIO5_29") (pintype "bidirectional"))
    )
    (net (code "26") (name "/GREEN") (class "Default")
      (node (ref "J12") (pin "5") (pinfunction "5_5") (pintype "passive"))
      (node (ref "U2") (pin "4") (pinfunction "QE_4") (pintype "tri_state"))
    )
    (net (code "27") (name "/LATCH_IN") (class "Default")
      (node (ref "U3") (pin "1") (pinfunction "SH/~{LD}_1") (pintype "input"))
      (node (ref "U4") (pin "1") (pinfunction "SH/~{LD}_1") (pintype "input"))
      (node (ref "U5") (pin "1") (pinfunction "SH/~{LD}_1") (pintype "input"))
      (node (ref "U6") (pin "22") (pinfunction "GPIO25/GPIO_GEN6_22") (pintype "bidirectional"))
    )
    (net (code "28") (name "/LATCH_OUT") (class "Default")
      (node (ref "U1") (pin "12") (pinfunction "RCLK_12") (pintype "input"))
      (node (ref "U2") (pin "12") (pinfunction "RCLK_12") (pintype "input"))
      (node (ref "U6") (pin "13") (pinfunction "GPIO27/GPIO_GEN2_13") (pintype "bidirectional"))
    )
    (net (code "29") (name "/LED_0") (class "Default")
      (node (ref "P1") (pin "2") (pinfunction "2_2") (pintype "passive"))
      (node (ref "U1") (pin "7") (pinfunction "QH_7") (pintype "tri_state"))
    )
    (net (code "30") (name "/LED_1") (class "Default")
      (node (ref "P2") (pin "2") (pinfunction "2_2") (pintype "passive"))
      (node (ref "U1") (pin "6") (pinfunction "QG_6") (pintype "tri_state"))
    )
    (net (code "31") (name "/LED_2") (class "Default")
      (node (ref "P3") (pin "2") (pinfunction "2_2") (pintype "passive"))
      (node (ref "U1") (pin "5") (pinfunction "QF_5") (pintype "tri_state"))
    )
    (net (code "32") (name "/LED_BLUE") (class "Default")
      (node (ref "P4") (pin "3") (pinfunction "3_3") (pintype "passive"))
      (node (ref "U1") (pin "3") (pinfunction "QD_3") (pintype "tri_state"))
    )
    (net (code "33") (name "/LED_GREEN") (class "Default")
      (node (ref "P4") (pin "4") (pinfunction "4_4") (pintype "passive"))
      (node (ref "U1") (pin "2") (pinfunction "QC_2") (pintype "tri_state"))
    )
    (net (code "34") (name "/LED_RED") (class "Default")
      (node (ref "P4") (pin "2") (pinfunction "2_2") (pintype "passive"))
      (node (ref "U1") (pin "4") (pinfunction "QE_4") (pintype "tri_state"))
    )
    (net (code "35") (name "/LID") (class "Default")
      (node (ref "J12") (pin "2") (pinfunction "2_2") (pintype "passive"))
      (node (ref "U5") (pin "6") (pinfunction "H_6") (pintype "input"))
    )
    (net (code "36") (name "/LIFT") (class "Default")
      (node (ref "J12") (pin "9") (pinfunction "9_9") (pintype "passive"))
      (node (ref "U6") (pin "19") (pinfunction "GPIO10/SPI_MOSI_19") (pintype "bidirectional"))
    )
    (net (code "37") (name "/LIMIT_0") (class "Default")
      (node (ref "P16") (pin "2") (pinfunction "2_2") (pintype "passive"))
      (node (ref "U4") (pin "6") (pinfunction "H_6") (pintype "input"))
    )
    (net (code "38") (name "/LIMIT_1") (class "Default")
      (node (ref "P17") (pin "2") (pinfunction "2_2") (pintype "passive"))
      (node (ref "U4") (pin "5") (pinfunction "G_5") (pintype "input"))
    )
    (net (code "39") (name "/LIMIT_2") (class "Default")
      (node (ref "P18") (pin "2") (pinfunction "2_2") (pintype "passive"))
      (node (ref "U4") (pin "4") (pinfunction "F_4") (pintype "input"))
    )
    (net (code "40") (name "/MAIN_DIR") (class "Default")
      (node (ref "P20") (pin "3") (pinfunction "3_3") (pintype "passive"))
      (node (ref "U6") (pin "11") (pinfunction "GPIO17/GPIO_GEN0_11") (pintype "bidirectional"))
    )
    (net (code "41") (name "/MAIN_PWM") (class "Default")
      (node (ref "P20") (pin "4") (pinfunction "4_4") (pintype "passive"))
      (node (ref "U6") (pin "12") (pinfunction "GPIO18/GPIO_GEN1_12") (pintype "bidirectional"))
    )
    (net (code "42") (name "/MOT_FAN") (class "Default")
      (node (ref "P20") (pin "8") (pinfunction "8_8") (pintype "passive"))
      (node (ref "U2") (pin "7") (pinfunction "QH_7") (pintype "tri_state"))
    )
    (net (code "43") (name "/PUMP_1") (class "Default")
      (node (ref "J12") (pin "6") (pinfunction "6_6") (pintype "passive"))
      (node (ref "U2") (pin "3") (pinfunction "QD_3") (pintype "tri_state"))
    )
    (net (code "44") (name "/PUMP_2") (class "Default")
      (node (ref "J12") (pin "8") (pinfunction "8_8") (pintype "passive"))
      (node (ref "U2") (pin "2") (pinfunction "QC_2") (pintype "tri_state"))
    )
    (net (code "45") (name "/PUMP_3") (class "Default")
      (node (ref "J12") (pin "10") (pinfunction "10_10") (pintype "passive"))
      (node (ref "U2") (pin "1") (pinfunction "QB_1") (pintype "tri_state"))
    )
    (net (code "46") (name "/PUMP_4") (class "Default")
      (node (ref "J12") (pin "19") (pinfunction "19_19") (pintype "passive"))
      (node (ref "U2") (pin "15") (pinfunction "QA_15") (pintype "tri_state"))
    )
    (net (code "47") (name "/RED") (class "Default")
      (node (ref "J12") (pin "4") (pinfunction "4_4") (pintype "passive"))
      (node (ref "U2") (pin "5") (pinfunction "QF_5") (pintype "tri_state"))
    )
    (net (code "48") (name "/RPM_A") (class "Default")
      (node (ref "P20") (pin "5") (pinfunction "5_5") (pintype "passive"))
      (node (ref "U6") (pin "32") (pinfunction "GPIO12_32") (pintype "bidirectional"))
    )
    (net (code "49") (name "/RPM_B") (class "Default")
      (node (ref "P20") (pin "6") (pinfunction "6_6") (pintype "passive"))
      (node (ref "U6") (pin "33") (pinfunction "GPIO13_33") (pintype "bidirectional"))
    )
    (net (code "50") (name "/SCL") (class "Default")
      (node (ref "P19") (pin "1") (pinfunction "1_1") (pintype "passive"))
      (node (ref "R14") (pin "1") (pinfunction "1_1") (pintype "passive"))
      (node (ref "U6") (pin "5") (pinfunction "GPIO3/SCL1_5") (pintype "bidirectional"))
    )
    (net (code "51") (name "/SDA") (class "Default")
      (node (ref "P19") (pin "2") (pinfunction "2_2") (pintype "passive"))
      (node (ref "R15") (pin "1") (pinfunction "1_1") (pintype "passive"))
      (node (ref "U6") (pin "3") (pinfunction "GPIO2/SDA1_3") (pintype "bidirectional"))
    )
    (net (code "52") (name "/SERIAL_IN") (class "Default")
      (node (ref "U3") (pin "9") (pinfunction "QH_9") (pintype "output"))
      (node (ref "U6") (pin "16") (pinfunction "GPIO23/GPIO_GEN4_16") (pintype "bidirectional"))
    )
    (net (code "53") (name "/SERIAL_IN1") (class "Default")
      (node (ref "U3") (pin "10") (pinfunction "SER_10") (pintype "input"))
      (node (ref "U4") (pin "9") (pinfunction "QH_9") (pintype "output"))
    )
    (net (code "54") (name "/SERIAL_IN2") (class "Default")
      (node (ref "U4") (pin "10") (pinfunction "SER_10") (pintype "input"))
      (node (ref "U5") (pin "9") (pinfunction "QH_9") (pintype "output"))
    )
    (net (code "55") (name "/SR_OE") (class "Default")
      (node (ref "U1") (pin "13") (pinfunction "~{OE}_13") (pintype "input"))
      (node (ref "U2") (pin "13") (pinfunction "~{OE}_13") (pintype "input"))
      (node (ref "U6") (pin "15") (pinfunction "GPIO22/GPIO_GEN3_15") (pintype "bidirectional"))
    )
    (net (code "56") (name "/SR_RESET") (class "Default")
      (node (ref "U1") (pin "10") (pinfunction "~{SRCLR}_10") (pintype "input"))
      (node (ref "U2") (pin "10") (pinfunction "~{SRCLR}_10") (pintype "input"))
      (node (ref "U6") (pin "37") (pinfunction "GPIO26_37") (pintype "bidirectional"))
    )
    (net (code "57") (name "/STEP") (class "Default")
      (node (ref "U6") (pin "31") (pinfunction "GPIO6_31") (pintype "bidirectional"))
      (node (ref "U7") (pin "7") (pinfunction "STEP_7") (pintype "input"))
    )
    (net (code "58") (name "/SW_1") (class "Default")
      (node (ref "J12") (pin "11") (pinfunction "11_11") (pintype "passive"))
      (node (ref "U5") (pin "4") (pinfunction "F_4") (pintype "input"))
    )
    (net (code "59") (name "/SW_2") (class "Default")
      (node (ref "J12") (pin "13") (pinfunction "13_13") (pintype "passive"))
      (node (ref "U5") (pin "3") (pinfunction "E_3") (pintype "input"))
    )
    (net (code "60") (name "/SW_3") (class "Default")
      (node (ref "J12") (pin "14") (pinfunction "14_14") (pintype "passive"))
      (node (ref "U5") (pin "14") (pinfunction "D_14") (pintype "input"))
    )
    (net (code "61") (name "/TEMP") (class "Default")
      (node (ref "J12") (pin "12") (pinfunction "12_12") (pintype "passive"))
      (node (ref "J4") (pin "1") (pinfunction "1_1") (pintype "passive"))
      (node (ref "J5") (pin "1") (pinfunction "S_1") (pintype "passive"))
      (node (ref "P20") (pin "7") (pinfunction "7_7") (pintype "passive"))
      (node (ref "R12") (pin "2") (pinfunction "2_2") (pintype "passive"))
      (node (ref "U6") (pin "7") (pinfunction "GPIO4/GPIO_GCKL_7") (pintype "bidirectional"))
    )
    (net (code "62") (name "/TOUCH_0") (class "Default")
      (node (ref "P8") (pin "1") (pinfunction "1_1") (pintype "passive"))
      (node (ref "U3") (pin "6") (pinfunction "H_6") (pintype "input"))
    )
    (net (code "63") (name "/TOUCH_1") (class "Default")
      (node (ref "P9") (pin "1") (pinfunction "1_1") (pintype "passive"))
      (node (ref "U3") (pin "5") (pinfunction "G_5") (pintype "input"))
    )
    (net (code "64") (name "/TOUCH_2") (class "Default")
      (node (ref "P10") (pin "1") (pinfunction "1_1") (pintype "passive"))
      (node (ref "U3") (pin "4") (pinfunction "F_4") (pintype "input"))
    )
    (net (code "65") (name "/TOUCH_3") (class "Default")
      (node (ref "P11") (pin "1") (pinfunction "1_1") (pintype "passive"))
      (node (ref "U3") (pin "3") (pinfunction "E_3") (pintype "input"))
    )
    (net (code "66") (name "/TOUCH_4") (class "Default")
      (node (ref "P12") (pin "1") (pinfunction "1_1") (pintype "passive"))
      (node (ref "U3") (pin "14") (pinfunction "D_14") (pintype "input"))
    )
    (net (code "67") (name "/TOUCH_5") (class "Default")
      (node (ref "P13") (pin "1") (pinfunction "1_1") (pintype "passive"))
      (node (ref "U3") (pin "13") (pinfunction "C_13") (pintype "input"))
    )
    (net (code "68") (name "/TOUCH_6") (class "Default")
      (node (ref "P14") (pin "1") (pinfunction "1_1") (pintype "passive"))
      (node (ref "U3") (pin "12") (pinfunction "B_12") (pintype "input"))
    )
    (net (code "69") (name "/TOUCH_7") (class "Default")
      (node (ref "P15") (pin "1") (pinfunction "1_1") (pintype "passive"))
      (node (ref "U3") (pin "11") (pinfunction "A_11") (pintype "input"))
    )
    (net (code "70") (name "GND") (class "Default")
      (node (ref "C1") (pin "1") (pinfunction "1_1") (pintype "passive"))
      (node (ref "C2") (pin "1") (pinfunction "1_1") (pintype "passive"))
      (node (ref "C3") (pin "1") (pinfunction "1_1") (pintype "passive"))
      (node (ref "C4") (pin "1") (pinfunction "1_1") (pintype "passive"))
      (node (ref "C5") (pin "1") (pinfunction "1_1") (pintype "passive"))
      (node (ref "D2") (pin "1") (pinfunction "Cathode_1") (pintype "passive"))
      (node (ref "D3") (pin "1") (pinfunction "Cathode_1") (pintype "passive"))
      (node (ref "J10") (pin "3") (pinfunction "3_3") (pintype "passive"))
      (node (ref "J11") (pin "3") (pinfunction "3_3") (pintype "passive"))
      (node (ref "J12") (pin "20") (pinfunction "20_20") (pintype "passive"))
      (node (ref "J14") (pin "3") (pinfunction "3_3") (pintype "passive"))
      (node (ref "J15") (pin "3") (pinfunction "3_3") (pintype "passive"))
      (node (ref "J16") (pin "3") (pinfunction "3_3") (pintype "passive"))
      (node (ref "J4") (pin "3") (pinfunction "3_3") (pintype "passive"))
      (node (ref "J5") (pin "3") (pinfunction "-_3") (pintype "passive"))
      (node (ref "J6") (pin "2") (pinfunction "2_2") (pintype "passive"))
      (node (ref "J7") (pin "6") (pinfunction "6_6") (pintype "passive"))
      (node (ref "J9") (pin "3") (pinfunction "3_3") (pintype "passive"))
      (node (ref "P1") (pin "4") (pinfunction "4_4") (pintype "passive"))
      (node (ref "P10") (pin "4") (pinfunction "4_4") (pintype "passive"))
      (node (ref "P11") (pin "4") (pinfunction "4_4") (pintype "passive"))
      (node (ref "P12") (pin "4") (pinfunction "4_4") (pintype "passive"))
      (node (ref "P13") (pin "4") (pinfunction "4_4") (pintype "passive"))
      (node (ref "P14") (pin "4") (pinfunction "4_4") (pintype "passive"))
      (node (ref "P15") (pin "4") (pinfunction "4_4") (pintype "passive"))
      (node (ref "P16") (pin "4") (pinfunction "4_4") (pintype "passive"))
      (node (ref "P17") (pin "4") (pinfunction "4_4") (pintype "passive"))
      (node (ref "P18") (pin "4") (pinfunction "4_4") (pintype "passive"))
      (node (ref "P19") (pin "4") (pinfunction "4_4") (pintype "passive"))
      (node (ref "P2") (pin "4") (pinfunction "4_4") (pintype "passive"))
      (node (ref "P20") (pin "1") (pinfunction "1_1") (pintype "passive"))
      (node (ref "P3") (pin "4") (pinfunction "4_4") (pintype "passive"))
      (node (ref "P5") (pin "2") (pinfunction "2_2") (pintype "passive"))
      (node (ref "P6") (pin "2") (pinfunction "2_2") (pintype "passive"))
      (node (ref "P8") (pin "4") (pinfunction "4_4") (pintype "passive"))
      (node (ref "P9") (pin "4") (pinfunction "4_4") (pintype "passive"))
      (node (ref "Q1") (pin "3") (pinfunction "S_3") (pintype "passive"))
      (node (ref "Q2") (pin "3") (pinfunction "S_3") (pintype "passive"))
      (node (ref "R11") (pin "2") (pinfunction "2_2") (pintype "passive"))
      (node (ref "R13") (pin "2") (pinfunction "2_2") (pintype "passive"))
      (node (ref "R4") (pin "1") (pinfunction "1_1") (pintype "passive"))
      (node (ref "R5") (pin "1") (pinfunction "1_1") (pintype "passive"))
      (node (ref "U1") (pin "8") (pinfunction "GND_8") (pintype "power_in"))
      (node (ref "U2") (pin "8") (pinfunction "GND_8") (pintype "power_in"))
      (node (ref "U3") (pin "8") (pinfunction "GND_8") (pintype "power_in"))
      (node (ref "U4") (pin "8") (pinfunction "GND_8") (pintype "power_in"))
      (node (ref "U5") (pin "8") (pinfunction "GND_8") (pintype "power_in"))
      (node (ref "U6") (pin "14") (pinfunction "GND_14") (pintype "power_in"))
      (node (ref "U6") (pin "20") (pinfunction "GND_20") (pintype "power_in"))
      (node (ref "U6") (pin "25") (pinfunction "GND_25") (pintype "power_in"))
      (node (ref "U6") (pin "30") (pinfunction "GND_30") (pintype "power_in"))
      (node (ref "U6") (pin "34") (pinfunction "GND_34") (pintype "power_in"))
      (node (ref "U6") (pin "39") (pinfunction "GND_39") (pintype "power_in"))
      (node (ref "U6") (pin "6") (pinfunction "GND_6") (pintype "power_in"))
      (node (ref "U6") (pin "9") (pinfunction "GND_9") (pintype "power_in"))
      (node (ref "U7") (pin "9") (pinfunction "GND_9") (pintype "power_in"))
    )
    (net (code "71") (name "Net-(D1-Anode)") (class "Default")
      (node (ref "D1") (pin "2") (pinfunction "Anode_2") (pintype "passive"))
      (node (ref "R1") (pin "1") (pinfunction "1_1") (pintype "passive"))
    )
    (net (code "72") (name "Net-(D2-Anode)") (class "Default")
      (node (ref "D2") (pin "2") (pinfunction "Anode_2") (pintype "passive"))
      (node (ref "R2") (pin "1") (pinfunction "1_1") (pintype "passive"))
    )
    (net (code "73") (name "Net-(D3-Anode)") (class "Default")
      (node (ref "D3") (pin "2") (pinfunction "Anode_2") (pintype "passive"))
      (node (ref "R3") (pin "1") (pinfunction "1_1") (pintype "passive"))
    )
    (net (code "74") (name "Net-(D4-Anode)") (class "Default")
      (node (ref "D4") (pin "1") (pinfunction "Anode_1") (pintype "passive"))
      (node (ref "D5") (pin "1") (pinfunction "Cathode_1") (pintype "passive"))
      (node (ref "J1") (pin "2") (pinfunction "-_2") (pintype "passive"))
      (node (ref "J2") (pin "2") (pinfunction "-_2") (pintype "passive"))
      (node (ref "Q2") (pin "4") (pinfunction "D_4") (pintype "passive"))
    )
    (net (code "75") (name "Net-(D5-Anode)") (class "Default")
      (node (ref "D5") (pin "2") (pinfunction "Anode_2") (pintype "passive"))
      (node (ref "R6") (pin "1") (pinfunction "1_1") (pintype "passive"))
    )
    (net (code "76") (name "Net-(D6-Anode)") (class "Default")
      (node (ref "D6") (pin "2") (pinfunction "Anode_2") (pintype "passive"))
      (node (ref "R16") (pin "1") (pinfunction "1_1") (pintype "passive"))
    )
    (net (code "77") (name "Net-(D7-Anode)") (class "Default")
      (node (ref "D7") (pin "2") (pinfunction "Anode_2") (pintype "passive"))
      (node (ref "R17") (pin "1") (pinfunction "1_1") (pintype "passive"))
    )
    (net (code "78") (name "Net-(D8-Anode)") (class "Default")
      (node (ref "D8") (pin "2") (pinfunction "Anode_2") (pintype "passive"))
      (node (ref "R18") (pin "1") (pinfunction "1_1") (pintype "passive"))
    )
    (net (code "79") (name "Net-(D9-Anode)") (class "Default")
      (node (ref "D9") (pin "2") (pinfunction "Anode_2") (pintype "passive"))
      (node (ref "R19") (pin "1") (pinfunction "1_1") (pintype "passive"))
    )
    (net (code "80") (name "Net-(J8-Pad1)") (class "Default")
      (node (ref "J8") (pin "1") (pinfunction "1_1") (pintype "passive"))
      (node (ref "U6") (pin "2") (pinfunction "5V0_2") (pintype "power_in"))
      (node (ref "U6") (pin "4") (pinfunction "5V0_4") (pintype "power_in"))
    )
    (net (code "81") (name "Net-(Q1-D)") (class "Default")
      (node (ref "J3") (pin "2") (pinfunction "2_2") (pintype "passive"))
      (node (ref "Q1") (pin "4") (pinfunction "D_4") (pintype "passive"))
    )
    (net (code "82") (name "Net-(Q1-G)") (class "Default")
      (node (ref "Q1") (pin "1") (pinfunction "G_1") (pintype "passive"))
      (node (ref "R11") (pin "1") (pinfunction "1_1") (pintype "passive"))
      (node (ref "R9") (pin "2") (pinfunction "2_2") (pintype "passive"))
    )
    (net (code "83") (name "Net-(Q2-G)") (class "Default")
      (node (ref "Q2") (pin "1") (pinfunction "G_1") (pintype "passive"))
      (node (ref "R10") (pin "2") (pinfunction "2_2") (pintype "passive"))
      (node (ref "R13") (pin "1") (pinfunction "1_1") (pintype "passive"))
    )
    (net (code "84") (name "Net-(Q3-D)") (class "Default")
      (node (ref "J6") (pin "1") (pinfunction "1_1") (pintype "passive"))
      (node (ref "Q3") (pin "3") (pinfunction "D_3") (pintype "passive"))
      (node (ref "R8") (pin "1") (pinfunction "1_1") (pintype "passive"))
    )
    (net (code "85") (name "Net-(U4-A)") (class "Default")
      (node (ref "R5") (pin "2") (pinfunction "2_2") (pintype "passive"))
      (node (ref "U4") (pin "11") (pinfunction "A_11") (pintype "input"))
      (node (ref "U4") (pin "12") (pinfunction "B_12") (pintype "input"))
      (node (ref "U4") (pin "13") (pinfunction "C_13") (pintype "input"))
    )
    (net (code "86") (name "Net-(U5-A)") (class "Default")
      (node (ref "R4") (pin "2") (pinfunction "2_2") (pintype "passive"))
      (node (ref "U5") (pin "10") (pinfunction "SER_10") (pintype "input"))
      (node (ref "U5") (pin "11") (pinfunction "A_11") (pintype "input"))
    )
    (net (code "87") (name "Net-(U7-MS1)") (class "Default")
      (node (ref "J14") (pin "2") (pinfunction "2_2") (pintype "passive"))
      (node (ref "U7") (pin "2") (pinfunction "MS1_2") (pintype "input"))
    )
    (net (code "88") (name "Net-(U7-MS2)") (class "Default")
      (node (ref "J15") (pin "2") (pinfunction "2_2") (pintype "passive"))
      (node (ref "U7") (pin "3") (pinfunction "MS2_3") (pintype "input"))
    )
    (net (code "89") (name "Net-(U7-MS3)") (class "Default")
      (node (ref "J16") (pin "2") (pinfunction "2_2") (pintype "passive"))
      (node (ref "U7") (pin "4") (pinfunction "MS3_4") (pintype "input"))
    )
    (net (code "90") (name "Net-(U7-~{ENABLE})") (class "Default")
      (node (ref "J9") (pin "2") (pinfunction "2_2") (pintype "passive"))
      (node (ref "U7") (pin "1") (pinfunction "~{ENABLE}_1") (pintype "input"))
    )
    (net (code "91") (name "Net-(U7-~{RESET})") (class "Default")
      (node (ref "J10") (pin "2") (pinfunction "2_2") (pintype "passive"))
      (node (ref "U7") (pin "5") (pinfunction "~{RESET}_5") (pintype "input"))
    )
    (net (code "92") (name "Net-(U7-~{SLEEP})") (class "Default")
      (node (ref "J11") (pin "2") (pinfunction "2_2") (pintype "passive"))
      (node (ref "U7") (pin "6") (pinfunction "~{SLEEP}_6") (pintype "input"))
    )
    (net (code "93") (name "PGND") (class "Default")
      (node (ref "C6") (pin "2") (pinfunction "A_2") (pintype "passive"))
      (node (ref "D1") (pin "1") (pinfunction "Cathode_1") (pintype "passive"))
      (node (ref "P7") (pin "2") (pinfunction "2_2") (pintype "passive"))
      (node (ref "U7") (pin "15") (pinfunction "GND_15") (pintype "power_in"))
    )
    (net (code "94") (name "unconnected-(J7-Pad5)") (class "Default")
      (node (ref "J7") (pin "5") (pinfunction "5_5") (pintype "passive"))
    )
    (net (code "95") (name "unconnected-(J8-Pad2)") (class "Default")
      (node (ref "J8") (pin "2") (pinfunction "2_2") (pintype "passive"))
    )
    (net (code "96") (name "unconnected-(P1-Pad3)") (class "Default")
      (node (ref "P1") (pin "3") (pinfunction "3_3") (pintype "passive"))
    )
    (net (code "97") (name "unconnected-(P2-Pad3)") (class "Default")
      (node (ref "P2") (pin "3") (pinfunction "3_3") (pintype "passive"))
    )
    (net (code "98") (name "unconnected-(P3-Pad3)") (class "Default")
      (node (ref "P3") (pin "3") (pinfunction "3_3") (pintype "passive"))
    )
    (net (code "99") (name "unconnected-(P8-Pad2)") (class "Default")
      (node (ref "P8") (pin "2") (pinfunction "2_2") (pintype "passive"))
    )
    (net (code "100") (name "unconnected-(P9-Pad2)") (class "Default")
      (node (ref "P9") (pin "2") (pinfunction "2_2") (pintype "passive"))
    )
    (net (code "101") (name "unconnected-(P10-Pad2)") (class "Default")
      (node (ref "P10") (pin "2") (pinfunction "2_2") (pintype "passive"))
    )
    (net (code "102") (name "unconnected-(P11-Pad2)") (class "Default")
      (node (ref "P11") (pin "2") (pinfunction "2_2") (pintype "passive"))
    )
    (net (code "103") (name "unconnected-(P12-Pad2)") (class "Default")
      (node (ref "P12") (pin "2") (pinfunction "2_2") (pintype "passive"))
    )
    (net (code "104") (name "unconnected-(P13-Pad2)") (class "Default")
      (node (ref "P13") (pin "2") (pinfunction "2_2") (pintype "passive"))
    )
    (net (code "105") (name "unconnected-(P14-Pad2)") (class "Default")
      (node (ref "P14") (pin "2") (pinfunction "2_2") (pintype "passive"))
    )
    (net (code "106") (name "unconnected-(P15-Pad2)") (class "Default")
      (node (ref "P15") (pin "2") (pinfunction "2_2") (pintype "passive"))
    )
    (net (code "107") (name "unconnected-(P16-Pad3)") (class "Default")
      (node (ref "P16") (pin "3") (pinfunction "3_3") (pintype "passive"))
    )
    (net (code "108") (name "unconnected-(P17-Pad3)") (class "Default")
      (node (ref "P17") (pin "3") (pinfunction "3_3") (pintype "passive"))
    )
    (net (code "109") (name "unconnected-(P18-Pad3)") (class "Default")
      (node (ref "P18") (pin "3") (pinfunction "3_3") (pintype "passive"))
    )
    (net (code "110") (name "unconnected-(P19-Pad3)") (class "Default")
      (node (ref "P19") (pin "3") (pinfunction "3_3") (pintype "passive"))
    )
    (net (code "111") (name "unconnected-(P20-Pad9)") (class "Default")
      (node (ref "P20") (pin "9") (pinfunction "9_9") (pintype "passive"))
    )
    (net (code "112") (name "unconnected-(P20-Pad10)") (class "Default")
      (node (ref "P20") (pin "10") (pinfunction "10_10") (pintype "passive"))
    )
    (net (code "113") (name "unconnected-(U1-QH'-Pad9)") (class "Default")
      (node (ref "U1") (pin "9") (pinfunction "QH'_9") (pintype "output"))
    )
    (net (code "114") (name "unconnected-(U2-QH'-Pad9)") (class "Default")
      (node (ref "U2") (pin "9") (pinfunction "QH'_9") (pintype "output"))
    )
    (net (code "115") (name "unconnected-(U3-~{Q}H-Pad7)") (class "Default")
      (node (ref "U3") (pin "7") (pinfunction "~{Q}H_7") (pintype "output"))
    )
    (net (code "116") (name "unconnected-(U4-~{Q}H-Pad7)") (class "Default")
      (node (ref "U4") (pin "7") (pinfunction "~{Q}H_7") (pintype "output"))
    )
    (net (code "117") (name "unconnected-(U5-~{Q}H-Pad7)") (class "Default")
      (node (ref "U5") (pin "7") (pinfunction "~{Q}H_7") (pintype "output"))
    )
    (net (code "118") (name "unconnected-(U6-3V3-Pad1)") (class "Default")
      (node (ref "U6") (pin "1") (pinfunction "3V3_1") (pintype "power_in"))
    )
    (net (code "119") (name "unconnected-(U6-3V3-Pad17)") (class "Default")
      (node (ref "U6") (pin "17") (pinfunction "3V3_17") (pintype "power_in"))
    )
    (net (code "120") (name "unconnected-(U6-GPIO7{slash}!SPI_CE1!-Pad26)") (class "Default")
      (node (ref "U6") (pin "26") (pinfunction "GPIO7/!SPI_CE1!_26") (pintype "bidirectional"))
    )
    (net (code "121") (name "unconnected-(U6-GPIO8{slash}!SPI_CE0!-Pad24)") (class "Default")
      (node (ref "U6") (pin "24") (pinfunction "GPIO8/!SPI_CE0!_24") (pintype "bidirectional"))
    )
    (net (code "122") (name "unconnected-(U6-ID_SC-Pad28)") (class "Default")
      (node (ref "U6") (pin "28") (pinfunction "ID_SC_28") (pintype "bidirectional"))
    )
    (net (code "123") (name "unconnected-(U6-ID_SD-Pad27)") (class "Default")
      (node (ref "U6") (pin "27") (pinfunction "ID_SD_27") (pintype "bidirectional"))
    )
    (net (code "124") (name "unconnected-(U6-SHIELD-PadS1)") (class "Default")
      (node (ref "U6") (pin "S1") (pinfunction "SHIELD_S1") (pintype "power_in"))
    )
    (net (code "125") (name "unconnected-(U6-SHIELD-PadS2)") (class "Default")
      (node (ref "U6") (pin "S2") (pinfunction "SHIELD_S2") (pintype "power_in"))
    )
    (net (code "126") (name "unconnected-(U6-SHIELD-PadS3)") (class "Default")
      (node (ref "U6") (pin "S3") (pinfunction "SHIELD_S3") (pintype "power_in"))
    )
    (net (code "127") (name "unconnected-(U6-SHIELD-PadS4)") (class "Default")
      (node (ref "U6") (pin "S4") (pinfunction "SHIELD_S4") (pintype "power_in"))
    )
  )
)
